# combo-03.net
KiCad netlist of a schematic drawn in EAGLE
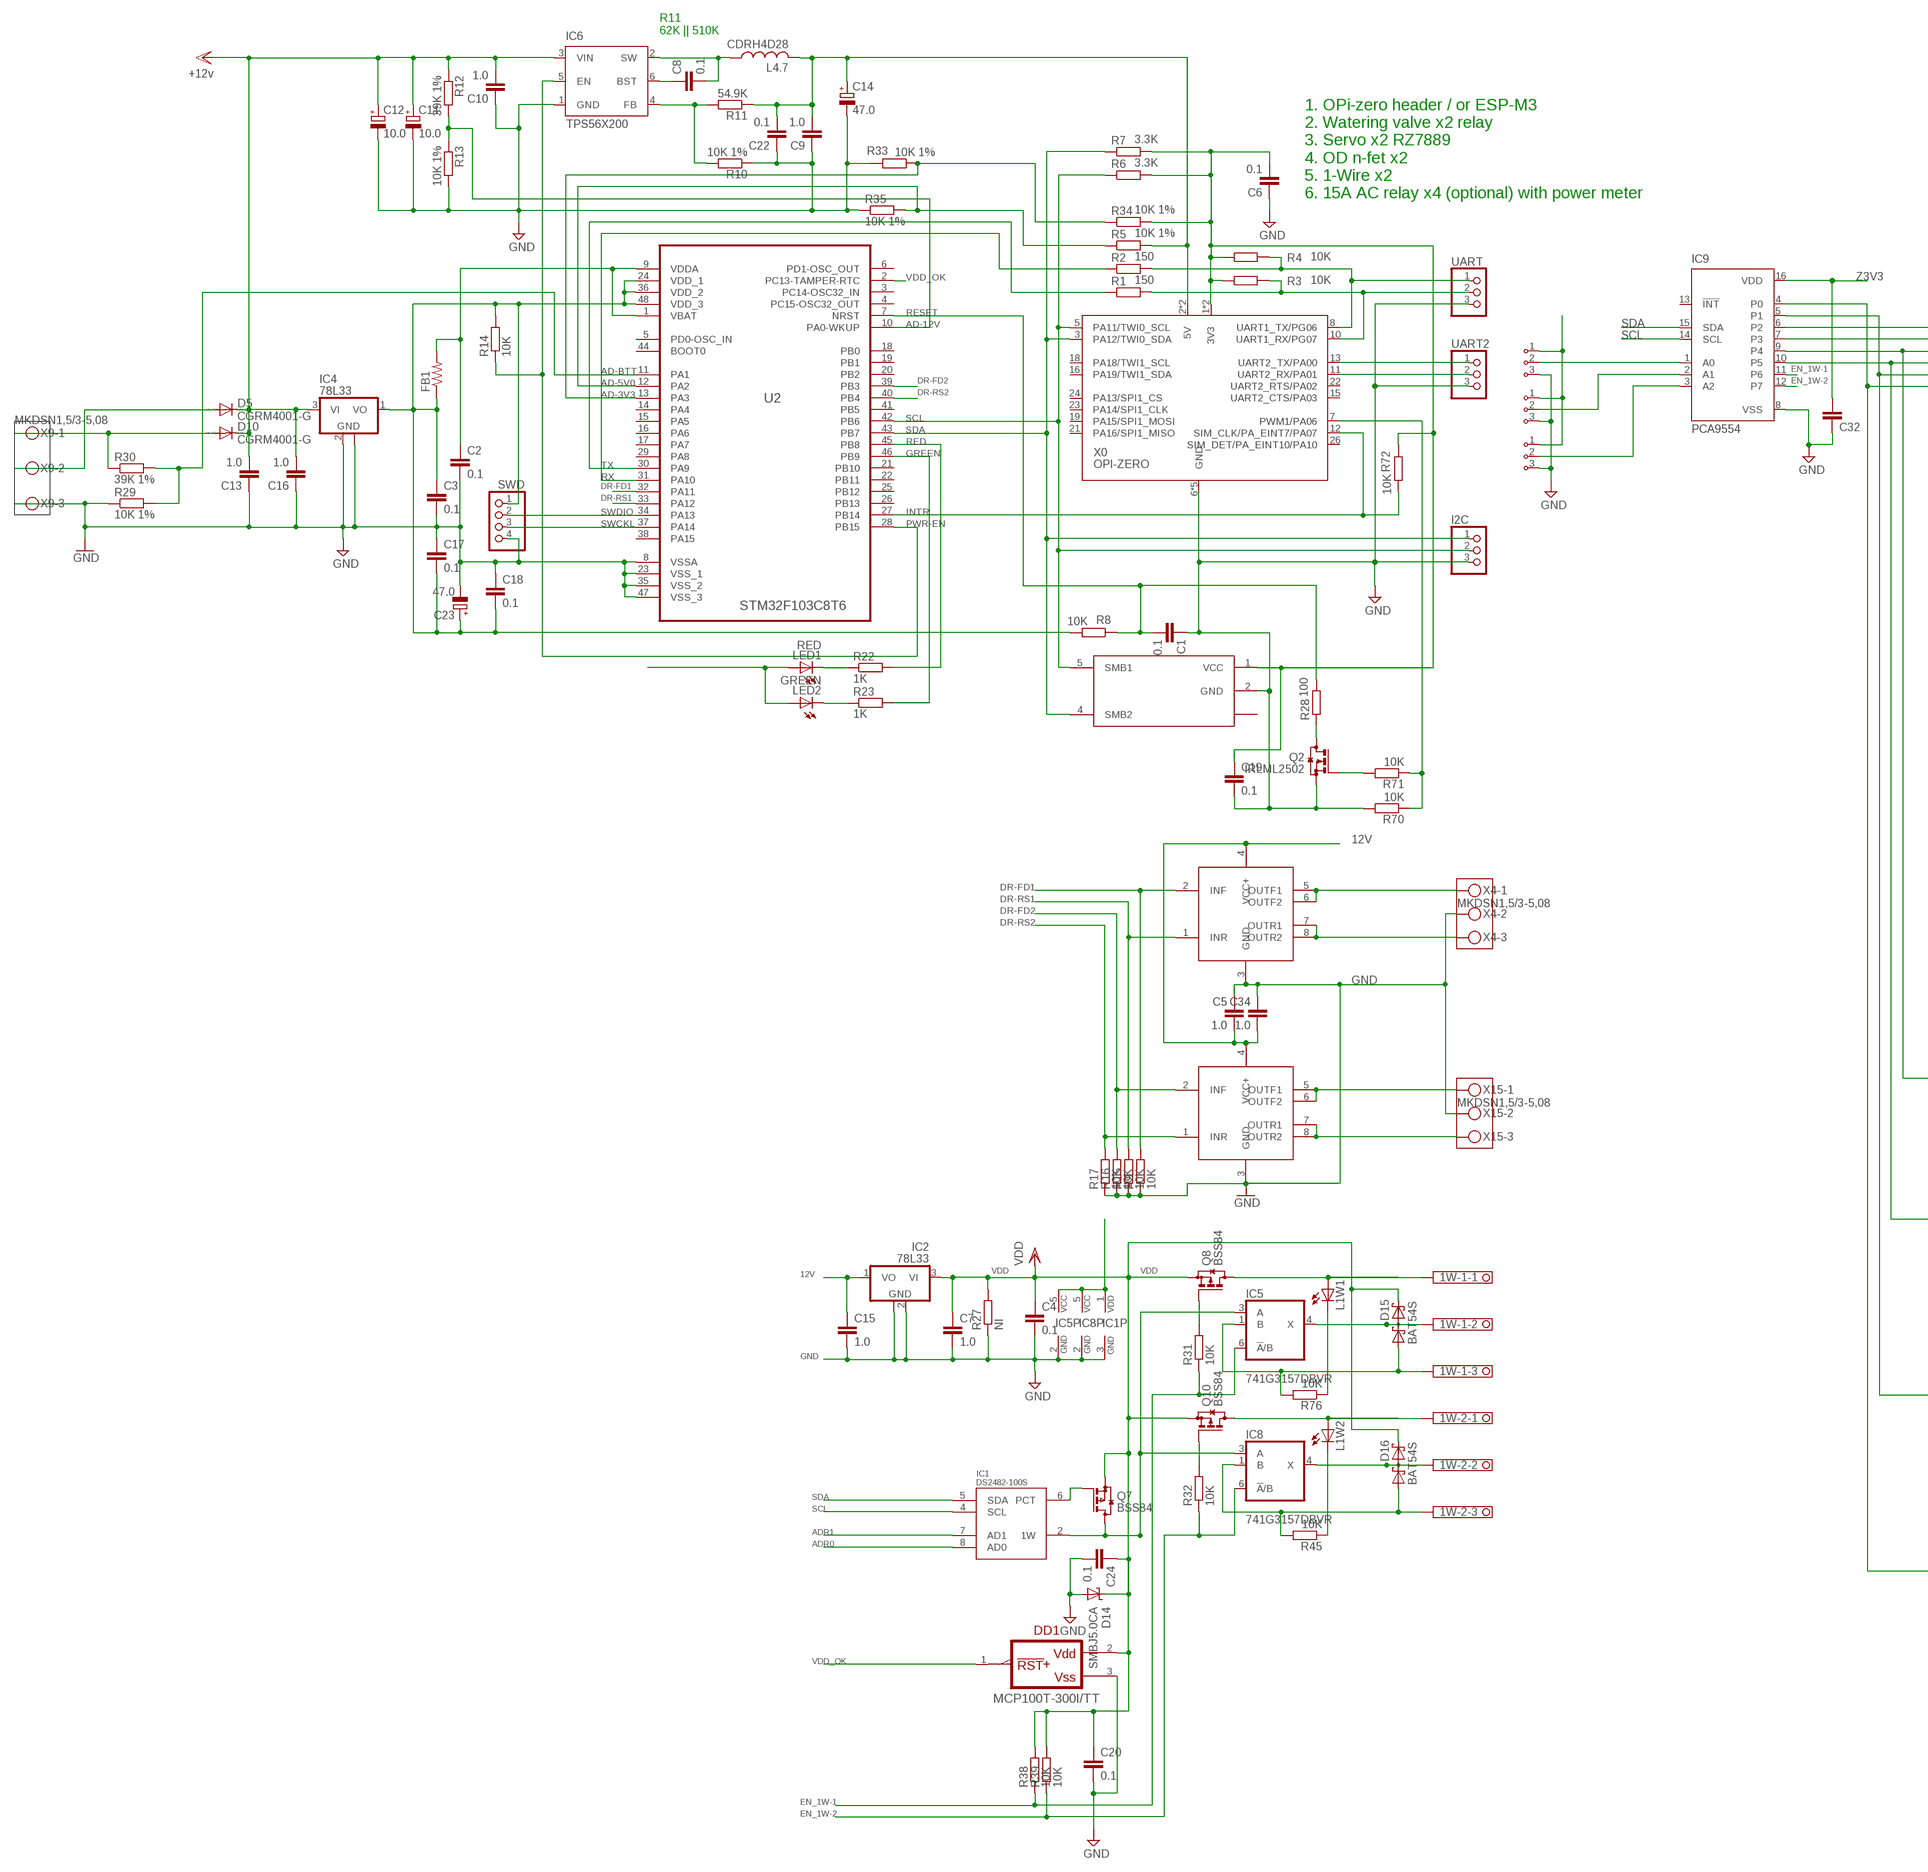
[diagram p0: schematic, sheet 1, part 1 of 2]
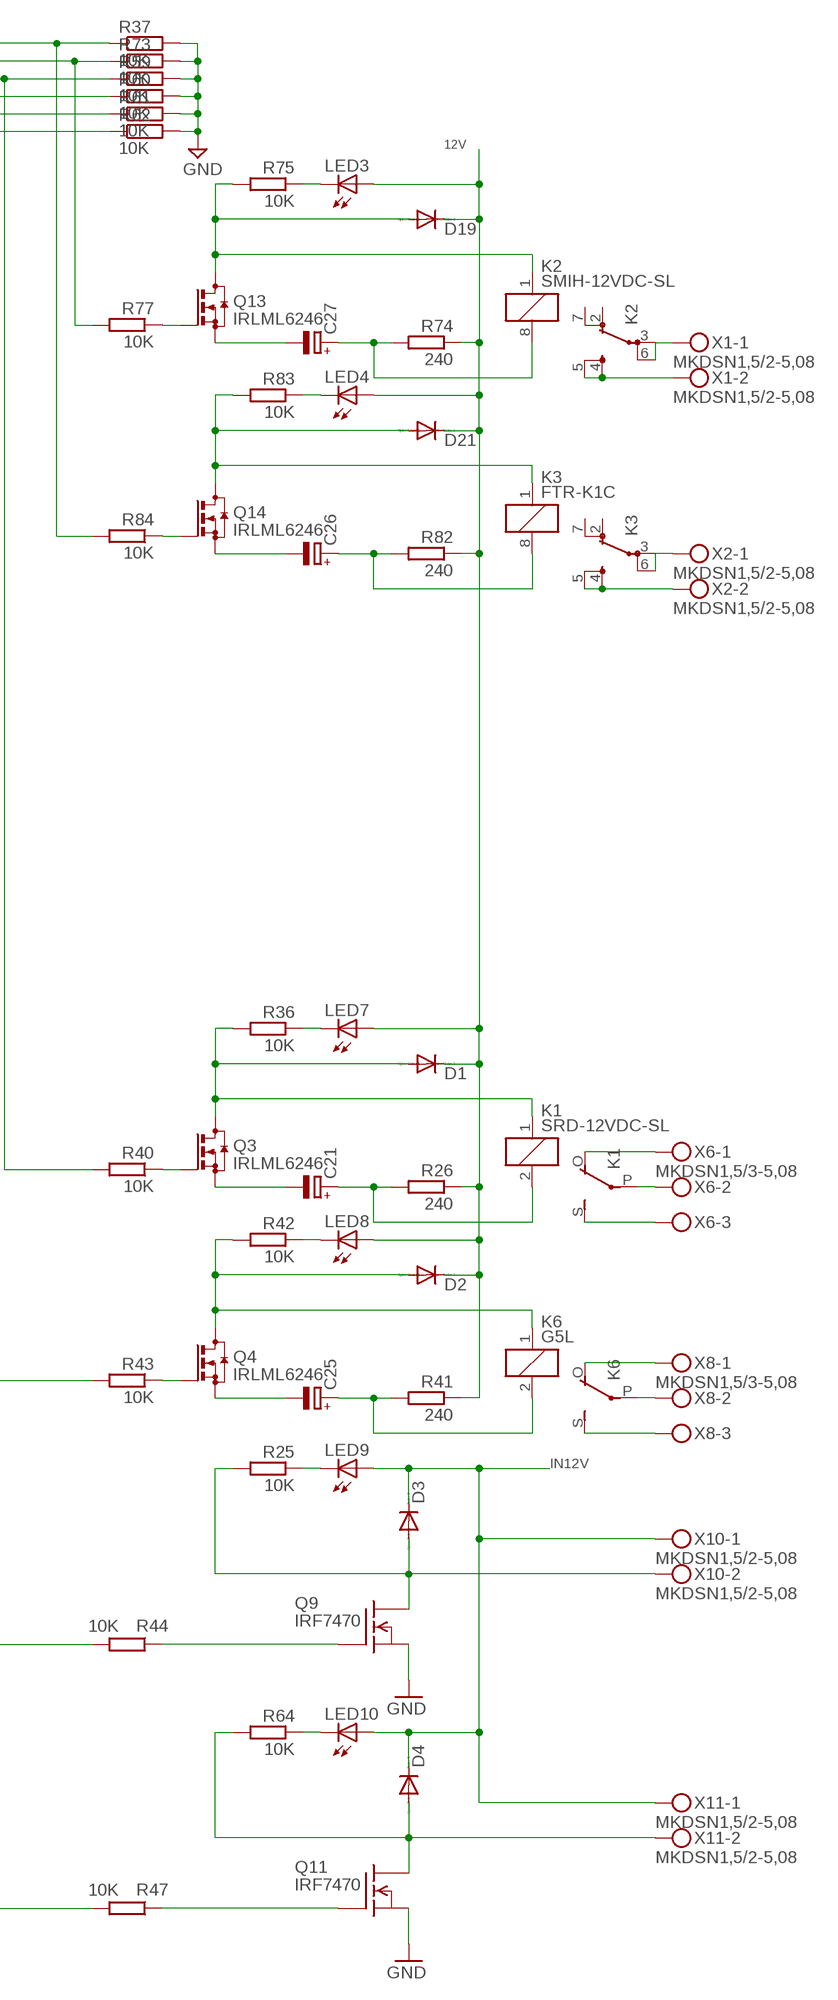
[diagram p1: schematic, sheet 1, part 2 of 2]

(export (version "E")
  (design (tool "Eeschema 10.0.6"))
  (components
    (comp (ref "1W-1")
      (value "1751251")
      (footprint "eagle-import:1751251")
      (libsource (lib "eagle-import") (part "1751251"))
    )
    (comp (ref "1W-2")
      (value "1751251")
      (footprint "eagle-import:1751251")
      (libsource (lib "eagle-import") (part "1751251"))
    )
    (comp (ref "A0")
      (value "ADDR3PIN0603")
      (footprint "eagle-import:0603-3PIN")
      (libsource (lib "eagle-import") (part "ADDR3PIN0603"))
    )
    (comp (ref "A1")
      (value "ADDR3PIN0603")
      (footprint "eagle-import:0603-3PIN")
      (libsource (lib "eagle-import") (part "ADDR3PIN0603"))
    )
    (comp (ref "A2")
      (value "ADDR3PIN0603")
      (footprint "eagle-import:0603-3PIN")
      (libsource (lib "eagle-import") (part "ADDR3PIN0603"))
    )
    (comp (ref "C1")
      (value "0.1")
      (footprint "eagle-import:C0603")
      (libsource (lib "eagle-import") (part "C-EUC0603"))
    )
    (comp (ref "C2")
      (value "0.1")
      (footprint "eagle-import:C0603")
      (libsource (lib "eagle-import") (part "C-EUC0603"))
    )
    (comp (ref "C3")
      (value "0.1")
      (footprint "eagle-import:C0603")
      (libsource (lib "eagle-import") (part "C-EUC0603"))
    )
    (comp (ref "C4")
      (value "0.1")
      (footprint "eagle-import:C0603")
      (libsource (lib "eagle-import") (part "C-EUC0603"))
    )
    (comp (ref "C5")
      (value "1.0")
      (footprint "eagle-import:C0805")
      (libsource (lib "eagle-import") (part "C-EUC0805"))
    )
    (comp (ref "C6")
      (value "0.1")
      (footprint "eagle-import:C0805")
      (libsource (lib "eagle-import") (part "C-EUC0805"))
    )
    (comp (ref "C7")
      (value "1.0")
      (footprint "eagle-import:C0805")
      (libsource (lib "eagle-import") (part "C-EUC0805"))
    )
    (comp (ref "C8")
      (value "0.1")
      (footprint "eagle-import:C0805")
      (libsource (lib "eagle-import") (part "C-EUC0805"))
    )
    (comp (ref "C9")
      (value "1.0")
      (footprint "eagle-import:C0805")
      (libsource (lib "eagle-import") (part "C-EUC0805"))
    )
    (comp (ref "C10")
      (value "1.0")
      (footprint "eagle-import:C1206")
      (libsource (lib "eagle-import") (part "C-EUC1206"))
    )
    (comp (ref "C11")
      (value "10.0")
      (footprint "eagle-import:C_6032-28R")
      (libsource (lib "eagle-import") (part "CPOL-EUC/6032-28R"))
    )
    (comp (ref "C12")
      (value "10.0")
      (footprint "eagle-import:C_6032-28R")
      (libsource (lib "eagle-import") (part "CPOL-EUC/6032-28R"))
    )
    (comp (ref "C13")
      (value "1.0")
      (footprint "eagle-import:C1206")
      (libsource (lib "eagle-import") (part "C-EUC1206"))
    )
    (comp (ref "C14")
      (value "47.0")
      (footprint "eagle-import:B_3528-21R")
      (libsource (lib "eagle-import") (part "CPOL-EUB/3528-21R"))
    )
    (comp (ref "C15")
      (value "1.0")
      (footprint "eagle-import:C0805")
      (libsource (lib "eagle-import") (part "C-EUC0805"))
    )
    (comp (ref "C16")
      (value "1.0")
      (footprint "eagle-import:C1206")
      (libsource (lib "eagle-import") (part "C-EUC1206"))
    )
    (comp (ref "C17")
      (value "0.1")
      (footprint "eagle-import:C0603")
      (libsource (lib "eagle-import") (part "C-EUC0603"))
    )
    (comp (ref "C18")
      (value "0.1")
      (footprint "eagle-import:C0603")
      (libsource (lib "eagle-import") (part "C-EUC0603"))
    )
    (comp (ref "C19")
      (value "0.1")
      (footprint "eagle-import:C0603")
      (libsource (lib "eagle-import") (part "C-EUC0603"))
    )
    (comp (ref "C20")
      (value "0.1")
      (footprint "eagle-import:C0603")
      (libsource (lib "eagle-import") (part "C-EUC0603"))
    )
    (comp (ref "C21")
      (value "CPOL-EUE3.5-8")
      (footprint "eagle-import:E3,5-8")
      (libsource (lib "eagle-import") (part "CPOL-EUE3.5-8"))
    )
    (comp (ref "C22")
      (value "0.1")
      (footprint "eagle-import:C0805")
      (libsource (lib "eagle-import") (part "C-EUC0805"))
    )
    (comp (ref "C23")
      (value "47.0")
      (footprint "eagle-import:B_3528-21R")
      (libsource (lib "eagle-import") (part "CPOL-EUB/3528-21R"))
    )
    (comp (ref "C24")
      (value "0.1")
      (footprint "eagle-import:C0603")
      (libsource (lib "eagle-import") (part "C-EUC0603"))
    )
    (comp (ref "C25")
      (value "CPOL-EUE3.5-8")
      (footprint "eagle-import:E3,5-8")
      (libsource (lib "eagle-import") (part "CPOL-EUE3.5-8"))
    )
    (comp (ref "C26")
      (value "CPOL-EUE3.5-8")
      (footprint "eagle-import:E3,5-8")
      (libsource (lib "eagle-import") (part "CPOL-EUE3.5-8"))
    )
    (comp (ref "C27")
      (value "CPOL-EUE3.5-8")
      (footprint "eagle-import:E3,5-8")
      (libsource (lib "eagle-import") (part "CPOL-EUE3.5-8"))
    )
    (comp (ref "C32")
      (value "C-EUC0805")
      (footprint "eagle-import:C0805")
      (libsource (lib "eagle-import") (part "C-EUC0805"))
    )
    (comp (ref "C34")
      (value "1.0")
      (footprint "eagle-import:C0805")
      (libsource (lib "eagle-import") (part "C-EUC0805"))
    )
    (comp (ref "D1")
      (value "DIODE-SOD123")
      (footprint "eagle-import:SOD123")
      (libsource (lib "eagle-import") (part "DIODE-SOD123"))
    )
    (comp (ref "D2")
      (value "DIODE-SOD123")
      (footprint "eagle-import:SOD123")
      (libsource (lib "eagle-import") (part "DIODE-SOD123"))
    )
    (comp (ref "D3")
      (value "DIODE-SOD123")
      (footprint "eagle-import:SOD123")
      (libsource (lib "eagle-import") (part "DIODE-SOD123"))
    )
    (comp (ref "D4")
      (value "DIODE-SOD123")
      (footprint "eagle-import:SOD123")
      (libsource (lib "eagle-import") (part "DIODE-SOD123"))
    )
    (comp (ref "D5")
      (value "CGRM4001-G")
      (footprint "eagle-import:SOD-123_MINI-SMA")
      (libsource (lib "eagle-import") (part "CGRM400-G1"))
    )
    (comp (ref "D10")
      (value "CGRM4001-G")
      (footprint "eagle-import:SOD-123_MINI-SMA")
      (libsource (lib "eagle-import") (part "CGRM400-G1"))
    )
    (comp (ref "D14")
      (value "SMBJ5.0CA")
      (footprint "eagle-import:SMBJ")
      (libsource (lib "eagle-import") (part "SUPPRESSOR-SMBJ"))
    )
    (comp (ref "D15")
      (value "BAT54S")
      (footprint "eagle-import:SOT23")
      (libsource (lib "eagle-import") (part "BAT54S"))
    )
    (comp (ref "D16")
      (value "BAT54S")
      (footprint "eagle-import:SOT23")
      (libsource (lib "eagle-import") (part "BAT54S"))
    )
    (comp (ref "D19")
      (value "DIODE-SOD123")
      (footprint "eagle-import:SOD123")
      (libsource (lib "eagle-import") (part "DIODE-SOD123"))
    )
    (comp (ref "D21")
      (value "DIODE-SOD123")
      (footprint "eagle-import:SOD123")
      (libsource (lib "eagle-import") (part "DIODE-SOD123"))
    )
    (comp (ref "DD1")
      (value "MCP100T-300I/TT")
      (footprint "eagle-import:SOT23")
      (libsource (lib "eagle-import") (part "MCP100T-300I/TT"))
    )
    (comp (ref "FB1")
      (value "R-US_R0805")
      (footprint "eagle-import:R0805")
      (libsource (lib "eagle-import") (part "R-US_R0805"))
    )
    (comp (ref "I2C")
      (value "PINHD-1X3")
      (footprint "eagle-import:1X03")
      (libsource (lib "eagle-import") (part "PINHD-1X3"))
    )
    (comp (ref "IC1")
      (value "DS2482-100S")
      (footprint "eagle-import:SO08")
      (libsource (lib "eagle-import") (part "DS2482-100S"))
    )
    (comp (ref "IC2")
      (value "78L33")
      (footprint "eagle-import:SOT89")
      (libsource (lib "eagle-import") (part "78LF05"))
    )
    (comp (ref "IC3")
      (value "RZ7889")
      (footprint "eagle-import:SO8")
      (libsource (lib "eagle-import") (part "RZ7889"))
    )
    (comp (ref "IC4")
      (value "78L33")
      (footprint "eagle-import:SOT89")
      (libsource (lib "eagle-import") (part "78LF05"))
    )
    (comp (ref "IC5")
      (value "741G3157DBVR")
      (footprint "eagle-import:DBV_R-PDSO-G6")
      (libsource (lib "eagle-import") (part "741G3157DBVR"))
    )
    (comp (ref "IC6")
      (value "TPS56X200")
      (footprint "eagle-import:TSOT23-6_DDC")
      (libsource (lib "eagle-import") (part "TPS56X200"))
    )
    (comp (ref "IC7")
      (value "LTC1694")
      (footprint "eagle-import:SOT23-5")
      (libsource (lib "eagle-import") (part "LTC1694"))
    )
    (comp (ref "IC8")
      (value "741G3157DBVR")
      (footprint "eagle-import:DBV_R-PDSO-G6")
      (libsource (lib "eagle-import") (part "741G3157DBVR"))
    )
    (comp (ref "IC9")
      (value "PCA9554")
      (footprint "eagle-import:SO16W")
      (fields (field (name "MPN") "PCF8574T/3,512"))
      (libsource (lib "eagle-import") (part "PCF8574T"))
    )
    (comp (ref "IC10")
      (value "RZ7889")
      (footprint "eagle-import:SO8")
      (libsource (lib "eagle-import") (part "RZ7889"))
    )
    (comp (ref "K1")
      (value "SRD-12VDC-SL")
      (footprint "eagle-import:G5LE")
      (libsource (lib "eagle-import") (part "G5L"))
    )
    (comp (ref "K2")
      (value "SMIH-12VDC-SL")
      (footprint "eagle-import:FTR-K1C")
      (libsource (lib "eagle-import") (part "FTR-K1C"))
    )
    (comp (ref "K3")
      (value "FTR-K1C")
      (footprint "eagle-import:FTR-K1C")
      (libsource (lib "eagle-import") (part "FTR-K1C"))
    )
    (comp (ref "K6")
      (value "G5L")
      (footprint "eagle-import:G5LE")
      (libsource (lib "eagle-import") (part "G5L"))
    )
    (comp (ref "L1W1")
      (value "LEDSMT1206")
      (footprint "eagle-import:1206")
      (libsource (lib "eagle-import") (part "LEDSMT1206"))
    )
    (comp (ref "L1W2")
      (value "LEDSMT1206")
      (footprint "eagle-import:1206")
      (libsource (lib "eagle-import") (part "LEDSMT1206"))
    )
    (comp (ref "L4.7")
      (value "CDRH4D28")
      (footprint "eagle-import:CDRH4D28")
      (libsource (lib "eagle-import") (part "CDRH4D28"))
    )
    (comp (ref "LED1")
      (value "RED")
      (footprint "eagle-import:CHIPLED_1206")
      (libsource (lib "eagle-import") (part "LEDCHIPLED_1206"))
    )
    (comp (ref "LED2")
      (value "GREEN")
      (footprint "eagle-import:CHIPLED_1206")
      (libsource (lib "eagle-import") (part "LEDCHIPLED_1206"))
    )
    (comp (ref "LED3")
      (value "LEDSMT1206")
      (footprint "eagle-import:1206")
      (libsource (lib "eagle-import") (part "LEDSMT1206"))
    )
    (comp (ref "LED4")
      (value "LEDSMT1206")
      (footprint "eagle-import:1206")
      (libsource (lib "eagle-import") (part "LEDSMT1206"))
    )
    (comp (ref "LED7")
      (value "LEDSMT1206")
      (footprint "eagle-import:1206")
      (libsource (lib "eagle-import") (part "LEDSMT1206"))
    )
    (comp (ref "LED8")
      (value "LEDSMT1206")
      (footprint "eagle-import:1206")
      (libsource (lib "eagle-import") (part "LEDSMT1206"))
    )
    (comp (ref "LED9")
      (value "LEDSMT1206")
      (footprint "eagle-import:1206")
      (libsource (lib "eagle-import") (part "LEDSMT1206"))
    )
    (comp (ref "LED10")
      (value "LEDSMT1206")
      (footprint "eagle-import:1206")
      (libsource (lib "eagle-import") (part "LEDSMT1206"))
    )
    (comp (ref "Q2")
      (value "IRLML2502")
      (footprint "eagle-import:SOT23")
      (libsource (lib "eagle-import") (part "IRLML2502"))
    )
    (comp (ref "Q3")
      (value "IRLML6246")
      (footprint "eagle-import:SOT23")
      (libsource (lib "eagle-import") (part "BSS123"))
    )
    (comp (ref "Q4")
      (value "IRLML6246")
      (footprint "eagle-import:SOT23")
      (libsource (lib "eagle-import") (part "BSS123"))
    )
    (comp (ref "Q7")
      (value "BSS84")
      (footprint "eagle-import:SOT23")
      (libsource (lib "eagle-import") (part "BSS84"))
    )
    (comp (ref "Q8")
      (value "BSS84")
      (footprint "eagle-import:SOT23")
      (libsource (lib "eagle-import") (part "BSS84"))
    )
    (comp (ref "Q9")
      (value "IRF7470")
      (footprint "eagle-import:SO-8")
      (libsource (lib "eagle-import") (part "FDS5680"))
    )
    (comp (ref "Q10")
      (value "BSS84")
      (footprint "eagle-import:SOT23")
      (libsource (lib "eagle-import") (part "BSS84"))
    )
    (comp (ref "Q11")
      (value "IRF7470")
      (footprint "eagle-import:SO-8")
      (libsource (lib "eagle-import") (part "FDS5680"))
    )
    (comp (ref "Q13")
      (value "IRLML6246")
      (footprint "eagle-import:SOT23")
      (libsource (lib "eagle-import") (part "BSS123"))
    )
    (comp (ref "Q14")
      (value "IRLML6246")
      (footprint "eagle-import:SOT23")
      (libsource (lib "eagle-import") (part "BSS123"))
    )
    (comp (ref "R1")
      (value "150")
      (footprint "eagle-import:R0603")
      (libsource (lib "eagle-import") (part "R-EU_R0603"))
    )
    (comp (ref "R2")
      (value "150")
      (footprint "eagle-import:R0603")
      (libsource (lib "eagle-import") (part "R-EU_R0603"))
    )
    (comp (ref "R3")
      (value "10K")
      (footprint "eagle-import:R0603")
      (libsource (lib "eagle-import") (part "R-EU_R0603"))
    )
    (comp (ref "R4")
      (value "10K")
      (footprint "eagle-import:R0603")
      (libsource (lib "eagle-import") (part "R-EU_R0603"))
    )
    (comp (ref "R5")
      (value "10K 1%")
      (footprint "eagle-import:R0603")
      (libsource (lib "eagle-import") (part "R-EU_R0603"))
    )
    (comp (ref "R6")
      (value "3.3K")
      (footprint "eagle-import:R0603")
      (libsource (lib "eagle-import") (part "R-EU_R0603"))
    )
    (comp (ref "R7")
      (value "3.3K")
      (footprint "eagle-import:R0603")
      (libsource (lib "eagle-import") (part "R-EU_R0603"))
    )
    (comp (ref "R8")
      (value "10K")
      (footprint "eagle-import:R0603")
      (libsource (lib "eagle-import") (part "R-EU_R0603"))
    )
    (comp (ref "R9")
      (value "10K")
      (footprint "eagle-import:R0603")
      (libsource (lib "eagle-import") (part "R-EU_R0603"))
    )
    (comp (ref "R10")
      (value "10K 1%")
      (footprint "eagle-import:R0603")
      (libsource (lib "eagle-import") (part "R-EU_R0603"))
    )
    (comp (ref "R11")
      (value "54.9K")
      (footprint "eagle-import:R0603")
      (libsource (lib "eagle-import") (part "R-EU_R0603"))
    )
    (comp (ref "R12")
      (value "39K 1%")
      (footprint "eagle-import:R0603")
      (libsource (lib "eagle-import") (part "R-EU_R0603"))
    )
    (comp (ref "R13")
      (value "10K 1%")
      (footprint "eagle-import:R0603")
      (libsource (lib "eagle-import") (part "R-EU_R0603"))
    )
    (comp (ref "R14")
      (value "10K")
      (footprint "eagle-import:R0603")
      (libsource (lib "eagle-import") (part "R-EU_R0603"))
    )
    (comp (ref "R15")
      (value "10K")
      (footprint "eagle-import:R0603")
      (libsource (lib "eagle-import") (part "R-EU_R0603"))
    )
    (comp (ref "R16")
      (value "10K")
      (footprint "eagle-import:R0603")
      (libsource (lib "eagle-import") (part "R-EU_R0603"))
    )
    (comp (ref "R17")
      (value "10K")
      (footprint "eagle-import:R0603")
      (libsource (lib "eagle-import") (part "R-EU_R0603"))
    )
    (comp (ref "R22")
      (value "1K")
      (footprint "eagle-import:R0603")
      (libsource (lib "eagle-import") (part "R-EU_R0603"))
    )
    (comp (ref "R23")
      (value "1K")
      (footprint "eagle-import:R0603")
      (libsource (lib "eagle-import") (part "R-EU_R0603"))
    )
    (comp (ref "R25")
      (value "10K")
      (footprint "eagle-import:R0603")
      (libsource (lib "eagle-import") (part "R-EU_R0603"))
    )
    (comp (ref "R26")
      (value "240")
      (footprint "eagle-import:R1206")
      (libsource (lib "eagle-import") (part "R-EU_R1206"))
    )
    (comp (ref "R27")
      (value "NI")
      (footprint "eagle-import:R0603")
      (libsource (lib "eagle-import") (part "R-EU_R0603"))
    )
    (comp (ref "R28")
      (value "100")
      (footprint "eagle-import:R0603")
      (libsource (lib "eagle-import") (part "R-EU_R0603"))
    )
    (comp (ref "R29")
      (value "10K 1%")
      (footprint "eagle-import:R0603")
      (libsource (lib "eagle-import") (part "R-EU_R0603"))
    )
    (comp (ref "R30")
      (value "39K 1%")
      (footprint "eagle-import:R0603")
      (libsource (lib "eagle-import") (part "R-EU_R0603"))
    )
    (comp (ref "R31")
      (value "10K")
      (footprint "eagle-import:R0603")
      (libsource (lib "eagle-import") (part "R-EU_R0603"))
    )
    (comp (ref "R32")
      (value "10K")
      (footprint "eagle-import:R0603")
      (libsource (lib "eagle-import") (part "R-EU_R0603"))
    )
    (comp (ref "R33")
      (value "10K 1%")
      (footprint "eagle-import:R0603")
      (libsource (lib "eagle-import") (part "R-EU_R0603"))
    )
    (comp (ref "R34")
      (value "10K 1%")
      (footprint "eagle-import:R0603")
      (libsource (lib "eagle-import") (part "R-EU_R0603"))
    )
    (comp (ref "R35")
      (value "10K 1%")
      (footprint "eagle-import:R0603")
      (libsource (lib "eagle-import") (part "R-EU_R0603"))
    )
    (comp (ref "R36")
      (value "10K")
      (footprint "eagle-import:R0603")
      (libsource (lib "eagle-import") (part "R-EU_R0603"))
    )
    (comp (ref "R37")
      (value "10K")
      (footprint "eagle-import:R0603")
      (libsource (lib "eagle-import") (part "R-EU_R0603"))
    )
    (comp (ref "R38")
      (value "10K")
      (footprint "eagle-import:R0603")
      (libsource (lib "eagle-import") (part "R-EU_R0603"))
    )
    (comp (ref "R39")
      (value "10K")
      (footprint "eagle-import:R0603")
      (libsource (lib "eagle-import") (part "R-EU_R0603"))
    )
    (comp (ref "R40")
      (value "10K")
      (footprint "eagle-import:R0603")
      (libsource (lib "eagle-import") (part "R-EU_R0603"))
    )
    (comp (ref "R41")
      (value "240")
      (footprint "eagle-import:R1206")
      (libsource (lib "eagle-import") (part "R-EU_R1206"))
    )
    (comp (ref "R42")
      (value "10K")
      (footprint "eagle-import:R0603")
      (libsource (lib "eagle-import") (part "R-EU_R0603"))
    )
    (comp (ref "R43")
      (value "10K")
      (footprint "eagle-import:R0603")
      (libsource (lib "eagle-import") (part "R-EU_R0603"))
    )
    (comp (ref "R44")
      (value "10K")
      (footprint "eagle-import:R0603")
      (libsource (lib "eagle-import") (part "R-EU_R0603"))
    )
    (comp (ref "R45")
      (value "10K")
      (footprint "eagle-import:R0603")
      (libsource (lib "eagle-import") (part "R-EU_R0603"))
    )
    (comp (ref "R47")
      (value "10K")
      (footprint "eagle-import:R0603")
      (libsource (lib "eagle-import") (part "R-EU_R0603"))
    )
    (comp (ref "R59")
      (value "10K")
      (footprint "eagle-import:R0603")
      (libsource (lib "eagle-import") (part "R-EU_R0603"))
    )
    (comp (ref "R60")
      (value "10K")
      (footprint "eagle-import:R0603")
      (libsource (lib "eagle-import") (part "R-EU_R0603"))
    )
    (comp (ref "R61")
      (value "10K")
      (footprint "eagle-import:R0603")
      (libsource (lib "eagle-import") (part "R-EU_R0603"))
    )
    (comp (ref "R62")
      (value "10K")
      (footprint "eagle-import:R0603")
      (libsource (lib "eagle-import") (part "R-EU_R0603"))
    )
    (comp (ref "R64")
      (value "10K")
      (footprint "eagle-import:R0603")
      (libsource (lib "eagle-import") (part "R-EU_R0603"))
    )
    (comp (ref "R70")
      (value "10K")
      (footprint "eagle-import:R0603")
      (libsource (lib "eagle-import") (part "R-EU_R0603"))
    )
    (comp (ref "R71")
      (value "10K")
      (footprint "eagle-import:R0603")
      (libsource (lib "eagle-import") (part "R-EU_R0603"))
    )
    (comp (ref "R72")
      (value "10K")
      (footprint "eagle-import:R0603")
      (libsource (lib "eagle-import") (part "R-EU_R0603"))
    )
    (comp (ref "R73")
      (value "10K")
      (footprint "eagle-import:R0603")
      (libsource (lib "eagle-import") (part "R-EU_R0603"))
    )
    (comp (ref "R74")
      (value "240")
      (footprint "eagle-import:R1206")
      (libsource (lib "eagle-import") (part "R-EU_R1206"))
    )
    (comp (ref "R75")
      (value "10K")
      (footprint "eagle-import:R0603")
      (libsource (lib "eagle-import") (part "R-EU_R0603"))
    )
    (comp (ref "R76")
      (value "10K")
      (footprint "eagle-import:R0603")
      (libsource (lib "eagle-import") (part "R-EU_R0603"))
    )
    (comp (ref "R77")
      (value "10K")
      (footprint "eagle-import:R0603")
      (libsource (lib "eagle-import") (part "R-EU_R0603"))
    )
    (comp (ref "R82")
      (value "240")
      (footprint "eagle-import:R1206")
      (libsource (lib "eagle-import") (part "R-EU_R1206"))
    )
    (comp (ref "R83")
      (value "10K")
      (footprint "eagle-import:R0603")
      (libsource (lib "eagle-import") (part "R-EU_R0603"))
    )
    (comp (ref "R84")
      (value "10K")
      (footprint "eagle-import:R0603")
      (libsource (lib "eagle-import") (part "R-EU_R0603"))
    )
    (comp (ref "SWD")
      (value "PINHD-1X4")
      (footprint "eagle-import:1X04")
      (libsource (lib "eagle-import") (part "PINHD-1X4"))
    )
    (comp (ref "U2")
      (value "STM32F103C8T6")
      (footprint "eagle-import:QFP50P900X900X160-48N")
      (fields (field (name "MPN") "STM32F100CBT6B"))
      (libsource (lib "eagle-import") (part "STM32F100CBT6B"))
    )
    (comp (ref "UART")
      (value "PINHD-1X3")
      (footprint "eagle-import:1X03")
      (libsource (lib "eagle-import") (part "PINHD-1X3"))
    )
    (comp (ref "UART2")
      (value "PINHD-1X3")
      (footprint "eagle-import:1X03")
      (libsource (lib "eagle-import") (part "PINHD-1X3"))
    )
    (comp (ref "X0")
      (value "OPI-ZERO")
      (footprint "eagle-import:OPI0")
      (libsource (lib "eagle-import") (part "OPI-ZERO"))
    )
    (comp (ref "X1")
      (value "MKDSN1,5/2-5,08")
      (footprint "eagle-import:MKDSN1,5_2-5,08")
      (libsource (lib "eagle-import") (part "MKDSN1,5/2-5,08"))
    )
    (comp (ref "X2")
      (value "MKDSN1,5/2-5,08")
      (footprint "eagle-import:MKDSN1,5_2-5,08")
      (libsource (lib "eagle-import") (part "MKDSN1,5/2-5,08"))
    )
    (comp (ref "X4")
      (value "MKDSN1,5/3-5,08")
      (footprint "eagle-import:MKDSN1,5_3-5,08")
      (libsource (lib "eagle-import") (part "MKDSN1,5/3-5,08"))
    )
    (comp (ref "X6")
      (value "MKDSN1,5/3-5,08")
      (footprint "eagle-import:MKDSN1,5_3-5,08")
      (libsource (lib "eagle-import") (part "MKDSN1,5/3-5,08"))
    )
    (comp (ref "X8")
      (value "MKDSN1,5/3-5,08")
      (footprint "eagle-import:MKDSN1,5_3-5,08")
      (libsource (lib "eagle-import") (part "MKDSN1,5/3-5,08"))
    )
    (comp (ref "X9")
      (value "MKDSN1,5/3-5,08")
      (footprint "eagle-import:MKDSN1,5_3-5,08")
      (libsource (lib "eagle-import") (part "MKDSN1,5/3-5,08"))
    )
    (comp (ref "X10")
      (value "MKDSN1,5/2-5,08")
      (footprint "eagle-import:MKDSN1,5_2-5,08")
      (libsource (lib "eagle-import") (part "MKDSN1,5/2-5,08"))
    )
    (comp (ref "X11")
      (value "MKDSN1,5/2-5,08")
      (footprint "eagle-import:MKDSN1,5_2-5,08")
      (libsource (lib "eagle-import") (part "MKDSN1,5/2-5,08"))
    )
    (comp (ref "X15")
      (value "MKDSN1,5/3-5,08")
      (footprint "eagle-import:MKDSN1,5_3-5,08")
      (libsource (lib "eagle-import") (part "MKDSN1,5/3-5,08"))
    )
  )
  (nets
    (net (code "1") (name "+12v") (class "Default")
      (node (ref "C10") (pin "2") (pinfunction "2_2") (pintype "passive"))
      (node (ref "C11") (pin "+") (pinfunction "+_+") (pintype "passive"))
      (node (ref "C12") (pin "+") (pinfunction "+_+") (pintype "passive"))
      (node (ref "C13") (pin "2") (pinfunction "2_2") (pintype "passive"))
      (node (ref "C15") (pin "1") (pinfunction "1_1") (pintype "passive"))
      (node (ref "C16") (pin "2") (pinfunction "2_2") (pintype "passive"))
      (node (ref "C34") (pin "2") (pinfunction "2_2") (pintype "passive"))
      (node (ref "C5") (pin "2") (pinfunction "2_2") (pintype "passive"))
      (node (ref "D1") (pin "C") (pinfunction "C_C") (pintype "passive"))
      (node (ref "D10") (pin "C") (pinfunction "C_C") (pintype "passive"))
      (node (ref "D19") (pin "C") (pinfunction "C_C") (pintype "passive"))
      (node (ref "D2") (pin "C") (pinfunction "C_C") (pintype "passive"))
      (node (ref "D21") (pin "C") (pinfunction "C_C") (pintype "passive"))
      (node (ref "D5") (pin "C") (pinfunction "C_C") (pintype "passive"))
      (node (ref "IC10") (pin "4") (pinfunction "VCC+_4") (pintype "bidirectional"))
      (node (ref "IC2") (pin "1") (pinfunction "VO_1") (pintype "passive"))
      (node (ref "IC3") (pin "4") (pinfunction "VCC+_4") (pintype "bidirectional"))
      (node (ref "IC4") (pin "3") (pinfunction "VI_3") (pintype "input"))
      (node (ref "IC6") (pin "3") (pinfunction "VIN_3") (pintype "input"))
      (node (ref "LED3") (pin "A") (pinfunction "A_A") (pintype "passive"))
      (node (ref "LED4") (pin "A") (pinfunction "A_A") (pintype "passive"))
      (node (ref "LED7") (pin "A") (pinfunction "A_A") (pintype "passive"))
      (node (ref "LED8") (pin "A") (pinfunction "A_A") (pintype "passive"))
      (node (ref "R12") (pin "1") (pinfunction "1_1") (pintype "passive"))
      (node (ref "R26") (pin "1") (pinfunction "1_1") (pintype "passive"))
      (node (ref "R41") (pin "1") (pinfunction "1_1") (pintype "passive"))
      (node (ref "R74") (pin "1") (pinfunction "1_1") (pintype "passive"))
      (node (ref "R82") (pin "1") (pinfunction "1_1") (pintype "passive"))
    )
    (net (code "2") (name "/AD-3V3") (class "Default")
      (node (ref "R33") (pin "1") (pinfunction "1_1") (pintype "passive"))
      (node (ref "R34") (pin "1") (pinfunction "1_1") (pintype "passive"))
      (node (ref "U2") (pin "13") (pinfunction "PA3_13") (pintype "bidirectional"))
    )
    (net (code "3") (name "/AD-5V0") (class "Default")
      (node (ref "R35") (pin "2") (pinfunction "2_2") (pintype "passive"))
      (node (ref "R5") (pin "1") (pinfunction "1_1") (pintype "passive"))
      (node (ref "U2") (pin "12") (pinfunction "PA2_12") (pintype "bidirectional"))
    )
    (net (code "4") (name "/AD-12V") (class "Default")
      (node (ref "R12") (pin "2") (pinfunction "2_2") (pintype "passive"))
      (node (ref "R13") (pin "1") (pinfunction "1_1") (pintype "passive"))
      (node (ref "U2") (pin "10") (pinfunction "PA0-WKUP_10") (pintype "bidirectional"))
    )
    (net (code "5") (name "/AD-BTT") (class "Default")
      (node (ref "R29") (pin "2") (pinfunction "2_2") (pintype "passive"))
      (node (ref "R30") (pin "2") (pinfunction "2_2") (pintype "passive"))
      (node (ref "U2") (pin "11") (pinfunction "PA1_11") (pintype "bidirectional"))
    )
    (net (code "6") (name "/ADR0") (class "Default")
      (node (ref "A2") (pin "2") (pinfunction "P$1_2") (pintype "bidirectional"))
      (node (ref "IC1") (pin "8") (pinfunction "AD0_8") (pintype "input"))
      (node (ref "IC9") (pin "1") (pinfunction "A0_1") (pintype "input"))
    )
    (net (code "7") (name "/ADR1") (class "Default")
      (node (ref "A1") (pin "2") (pinfunction "P$1_2") (pintype "bidirectional"))
      (node (ref "IC1") (pin "7") (pinfunction "AD1_7") (pintype "input"))
      (node (ref "IC9") (pin "2") (pinfunction "A1_2") (pintype "input"))
    )
    (net (code "8") (name "/DR-FD1") (class "Default")
      (node (ref "IC3") (pin "2") (pinfunction "INF_2") (pintype "bidirectional"))
      (node (ref "R9") (pin "2") (pinfunction "2_2") (pintype "passive"))
      (node (ref "U2") (pin "32") (pinfunction "PA11_32") (pintype "bidirectional"))
    )
    (net (code "9") (name "/DR-FD2") (class "Default")
      (node (ref "IC10") (pin "2") (pinfunction "INF_2") (pintype "bidirectional"))
      (node (ref "R16") (pin "2") (pinfunction "2_2") (pintype "passive"))
      (node (ref "U2") (pin "39") (pinfunction "PB3_39") (pintype "bidirectional"))
    )
    (net (code "10") (name "/DR-RS1") (class "Default")
      (node (ref "IC3") (pin "1") (pinfunction "INR_1") (pintype "bidirectional"))
      (node (ref "R15") (pin "2") (pinfunction "2_2") (pintype "passive"))
      (node (ref "U2") (pin "33") (pinfunction "PA12_33") (pintype "bidirectional"))
    )
    (net (code "11") (name "/DR-RS2") (class "Default")
      (node (ref "IC10") (pin "1") (pinfunction "INR_1") (pintype "bidirectional"))
      (node (ref "R17") (pin "2") (pinfunction "2_2") (pintype "passive"))
      (node (ref "U2") (pin "40") (pinfunction "PB4_40") (pintype "bidirectional"))
    )
    (net (code "12") (name "/EN_1W-1") (class "Default")
      (node (ref "IC5") (pin "6") (pinfunction "~{A}/B_6") (pintype "input"))
      (node (ref "IC9") (pin "11") (pinfunction "P6_11") (pintype "bidirectional"))
      (node (ref "R31") (pin "1") (pinfunction "1_1") (pintype "passive"))
      (node (ref "R38") (pin "1") (pinfunction "1_1") (pintype "passive"))
    )
    (net (code "13") (name "/EN_1W-2") (class "Default")
      (node (ref "IC8") (pin "6") (pinfunction "~{A}/B_6") (pintype "input"))
      (node (ref "IC9") (pin "12") (pinfunction "P7_12") (pintype "bidirectional"))
      (node (ref "R32") (pin "1") (pinfunction "1_1") (pintype "passive"))
      (node (ref "R39") (pin "1") (pinfunction "1_1") (pintype "passive"))
    )
    (net (code "14") (name "/GREEN") (class "Default")
      (node (ref "R23") (pin "2") (pinfunction "2_2") (pintype "passive"))
      (node (ref "U2") (pin "46") (pinfunction "PB9_46") (pintype "bidirectional"))
    )
    (net (code "15") (name "/IN12V") (class "Default")
      (node (ref "D3") (pin "C") (pinfunction "C_C") (pintype "passive"))
      (node (ref "D4") (pin "C") (pinfunction "C_C") (pintype "passive"))
      (node (ref "D5") (pin "A") (pinfunction "A_A") (pintype "passive"))
      (node (ref "LED10") (pin "A") (pinfunction "A_A") (pintype "passive"))
      (node (ref "LED9") (pin "A") (pinfunction "A_A") (pintype "passive"))
      (node (ref "X10") (pin "1") (pinfunction "KL_1") (pintype "passive"))
      (node (ref "X11") (pin "1") (pinfunction "KL_1") (pintype "passive"))
      (node (ref "X9") (pin "2") (pinfunction "KL_2") (pintype "passive"))
    )
    (net (code "16") (name "/INTR") (class "Default")
      (node (ref "R72") (pin "2") (pinfunction "2_2") (pintype "passive"))
      (node (ref "U2") (pin "27") (pinfunction "PB14_27") (pintype "bidirectional"))
      (node (ref "X0") (pin "12") (pinfunction "SIM_CLK/PA_EINT7/PA07_12") (pintype "bidirectional"))
    )
    (net (code "17") (name "/PWR-EN") (class "Default")
      (node (ref "IC6") (pin "5") (pinfunction "EN_5") (pintype "input"))
      (node (ref "R14") (pin "1") (pinfunction "1_1") (pintype "passive"))
      (node (ref "U2") (pin "28") (pinfunction "PB15_28") (pintype "bidirectional"))
    )
    (net (code "18") (name "/RED") (class "Default")
      (node (ref "R22") (pin "2") (pinfunction "2_2") (pintype "passive"))
      (node (ref "U2") (pin "45") (pinfunction "PB8_45") (pintype "bidirectional"))
    )
    (net (code "19") (name "/RESET") (class "Default")
      (node (ref "C1") (pin "2") (pinfunction "2_2") (pintype "passive"))
      (node (ref "R28") (pin "2") (pinfunction "2_2") (pintype "passive"))
      (node (ref "R8") (pin "1") (pinfunction "1_1") (pintype "passive"))
      (node (ref "U2") (pin "7") (pinfunction "NRST_7") (pintype "bidirectional"))
    )
    (net (code "20") (name "/RX") (class "Default")
      (node (ref "R2") (pin "1") (pinfunction "1_1") (pintype "passive"))
      (node (ref "U2") (pin "31") (pinfunction "PA10_31") (pintype "bidirectional"))
    )
    (net (code "21") (name "/SCL") (class "Default")
      (node (ref "I2C") (pin "2") (pinfunction "2_2") (pintype "passive"))
      (node (ref "IC1") (pin "4") (pinfunction "SCL_4") (pintype "input"))
      (node (ref "IC7") (pin "5") (pinfunction "SMB1_5") (pintype "bidirectional"))
      (node (ref "IC9") (pin "14") (pinfunction "SCL_14") (pintype "input"))
      (node (ref "R6") (pin "1") (pinfunction "1_1") (pintype "passive"))
      (node (ref "U2") (pin "42") (pinfunction "PB6_42") (pintype "bidirectional"))
      (node (ref "X0") (pin "5") (pinfunction "PA11/TWI0_SCL_5") (pintype "bidirectional"))
    )
    (net (code "22") (name "/SDA") (class "Default")
      (node (ref "I2C") (pin "1") (pinfunction "1_1") (pintype "passive"))
      (node (ref "IC1") (pin "5") (pinfunction "SDA_5") (pintype "bidirectional"))
      (node (ref "IC7") (pin "4") (pinfunction "SMB2_4") (pintype "bidirectional"))
      (node (ref "IC9") (pin "15") (pinfunction "SDA_15") (pintype "bidirectional"))
      (node (ref "R7") (pin "1") (pinfunction "1_1") (pintype "passive"))
      (node (ref "U2") (pin "43") (pinfunction "PB7_43") (pintype "bidirectional"))
      (node (ref "X0") (pin "3") (pinfunction "PA12/TWI0_SDA_3") (pintype "bidirectional"))
    )
    (net (code "23") (name "/SWCKL") (class "Default")
      (node (ref "SWD") (pin "3") (pinfunction "3_3") (pintype "passive"))
      (node (ref "U2") (pin "37") (pinfunction "PA14_37") (pintype "bidirectional"))
    )
    (net (code "24") (name "/SWDIO") (class "Default")
      (node (ref "SWD") (pin "2") (pinfunction "2_2") (pintype "passive"))
      (node (ref "U2") (pin "34") (pinfunction "PA13_34") (pintype "bidirectional"))
    )
    (net (code "25") (name "/TX") (class "Default")
      (node (ref "R1") (pin "1") (pinfunction "1_1") (pintype "passive"))
      (node (ref "U2") (pin "30") (pinfunction "PA9_30") (pintype "bidirectional"))
    )
    (net (code "26") (name "/VDD_OK") (class "Default")
      (node (ref "DD1") (pin "1") (pinfunction "~{RST}_1") (pintype "passive"))
      (node (ref "U2") (pin "2") (pinfunction "PC13-TAMPER-RTC_2") (pintype "bidirectional"))
    )
    (net (code "27") (name "/Z3V3") (class "Default")
      (node (ref "A0") (pin "1") (pinfunction "P$2_1") (pintype "power_in"))
      (node (ref "A1") (pin "1") (pinfunction "P$2_1") (pintype "power_in"))
      (node (ref "A2") (pin "1") (pinfunction "P$2_1") (pintype "power_in"))
      (node (ref "C19") (pin "1") (pinfunction "1_1") (pintype "passive"))
      (node (ref "C32") (pin "2") (pinfunction "2_2") (pintype "passive"))
      (node (ref "C6") (pin "2") (pinfunction "2_2") (pintype "passive"))
      (node (ref "IC1") (pin "1") (pinfunction "VDD_1") (pintype "power_in"))
      (node (ref "IC5") (pin "5") (pinfunction "VCC_5") (pintype "power_in"))
      (node (ref "IC7") (pin "1") (pinfunction "VCC_1") (pintype "power_in"))
      (node (ref "IC8") (pin "5") (pinfunction "VCC_5") (pintype "power_in"))
      (node (ref "IC9") (pin "16") (pinfunction "VDD_16") (pintype "power_in"))
      (node (ref "R3") (pin "1") (pinfunction "1_1") (pintype "passive"))
      (node (ref "R34") (pin "2") (pinfunction "2_2") (pintype "passive"))
      (node (ref "R4") (pin "1") (pinfunction "1_1") (pintype "passive"))
      (node (ref "R6") (pin "2") (pinfunction "2_2") (pintype "passive"))
      (node (ref "R7") (pin "2") (pinfunction "2_2") (pintype "passive"))
      (node (ref "R72") (pin "1") (pinfunction "1_1") (pintype "passive"))
      (node (ref "X0") (pin "1") (pinfunction "3V3_1") (pintype "power_in"))
      (node (ref "X0") (pin "17") (pinfunction "3V3_17") (pintype "power_in"))
    )
    (net (code "28") (name "GND") (class "Default")
      (node (ref "1W-1") (pin "3") (pinfunction "K_3") (pintype "passive"))
      (node (ref "1W-2") (pin "3") (pinfunction "K_3") (pintype "passive"))
      (node (ref "A0") (pin "3") (pinfunction "P$3_3") (pintype "power_in"))
      (node (ref "A1") (pin "3") (pinfunction "P$3_3") (pintype "power_in"))
      (node (ref "A2") (pin "3") (pinfunction "P$3_3") (pintype "power_in"))
      (node (ref "C1") (pin "1") (pinfunction "1_1") (pintype "passive"))
      (node (ref "C10") (pin "1") (pinfunction "1_1") (pintype "passive"))
      (node (ref "C11") (pin "-") (pinfunction "-_-") (pintype "passive"))
      (node (ref "C12") (pin "-") (pinfunction "-_-") (pintype "passive"))
      (node (ref "C13") (pin "1") (pinfunction "1_1") (pintype "passive"))
      (node (ref "C14") (pin "-") (pinfunction "-_-") (pintype "passive"))
      (node (ref "C15") (pin "2") (pinfunction "2_2") (pintype "passive"))
      (node (ref "C16") (pin "1") (pinfunction "1_1") (pintype "passive"))
      (node (ref "C17") (pin "1") (pinfunction "1_1") (pintype "passive"))
      (node (ref "C18") (pin "1") (pinfunction "1_1") (pintype "passive"))
      (node (ref "C19") (pin "2") (pinfunction "2_2") (pintype "passive"))
      (node (ref "C2") (pin "2") (pinfunction "2_2") (pintype "passive"))
      (node (ref "C20") (pin "2") (pinfunction "2_2") (pintype "passive"))
      (node (ref "C21") (pin "-") (pinfunction "-_-") (pintype "passive"))
      (node (ref "C22") (pin "1") (pinfunction "1_1") (pintype "passive"))
      (node (ref "C23") (pin "-") (pinfunction "-_-") (pintype "passive"))
      (node (ref "C24") (pin "2") (pinfunction "2_2") (pintype "passive"))
      (node (ref "C25") (pin "-") (pinfunction "-_-") (pintype "passive"))
      (node (ref "C26") (pin "-") (pinfunction "-_-") (pintype "passive"))
      (node (ref "C27") (pin "-") (pinfunction "-_-") (pintype "passive"))
      (node (ref "C3") (pin "2") (pinfunction "2_2") (pintype "passive"))
      (node (ref "C32") (pin "1") (pinfunction "1_1") (pintype "passive"))
      (node (ref "C34") (pin "1") (pinfunction "1_1") (pintype "passive"))
      (node (ref "C4") (pin "2") (pinfunction "2_2") (pintype "passive"))
      (node (ref "C5") (pin "1") (pinfunction "1_1") (pintype "passive"))
      (node (ref "C6") (pin "1") (pinfunction "1_1") (pintype "passive"))
      (node (ref "C7") (pin "2") (pinfunction "2_2") (pintype "passive"))
      (node (ref "C9") (pin "1") (pinfunction "1_1") (pintype "passive"))
      (node (ref "D14") (pin "A") (pinfunction "A_A") (pintype "passive"))
      (node (ref "D15") (pin "1") (pinfunction "A1_1") (pintype "passive"))
      (node (ref "D16") (pin "1") (pinfunction "A1_1") (pintype "passive"))
      (node (ref "DD1") (pin "3") (pinfunction "VSS_3") (pintype "passive"))
      (node (ref "I2C") (pin "3") (pinfunction "3_3") (pintype "passive"))
      (node (ref "IC1") (pin "3") (pinfunction "GND_3") (pintype "power_in"))
      (node (ref "IC10") (pin "3") (pinfunction "GND_3") (pintype "bidirectional"))
      (node (ref "IC2") (pin "2") (pinfunction "GND_2") (pintype "passive"))
      (node (ref "IC2") (pin "2@1") (pinfunction "GND_2@1") (pintype "passive"))
      (node (ref "IC3") (pin "3") (pinfunction "GND_3") (pintype "bidirectional"))
      (node (ref "IC4") (pin "2") (pinfunction "GND_2") (pintype "passive"))
      (node (ref "IC4") (pin "2@1") (pinfunction "GND_2@1") (pintype "passive"))
      (node (ref "IC5") (pin "1") (pinfunction "B_1") (pintype "bidirectional"))
      (node (ref "IC5") (pin "2") (pinfunction "GND_2") (pintype "power_in"))
      (node (ref "IC6") (pin "1") (pinfunction "GND_1") (pintype "power_in"))
      (node (ref "IC7") (pin "2") (pinfunction "GND_2") (pintype "power_in"))
      (node (ref "IC8") (pin "1") (pinfunction "B_1") (pintype "bidirectional"))
      (node (ref "IC8") (pin "2") (pinfunction "GND_2") (pintype "power_in"))
      (node (ref "IC9") (pin "8") (pinfunction "VSS_8") (pintype "power_in"))
      (node (ref "Q11") (pin "1") (pinfunction "S_1") (pintype "passive"))
      (node (ref "Q11") (pin "2") (pinfunction "S_2") (pintype "passive"))
      (node (ref "Q11") (pin "3") (pinfunction "S_3") (pintype "passive"))
      (node (ref "Q13") (pin "2") (pinfunction "S_2") (pintype "passive"))
      (node (ref "Q14") (pin "2") (pinfunction "S_2") (pintype "passive"))
      (node (ref "Q2") (pin "2") (pinfunction "S_2") (pintype "passive"))
      (node (ref "Q3") (pin "2") (pinfunction "S_2") (pintype "passive"))
      (node (ref "Q4") (pin "2") (pinfunction "S_2") (pintype "passive"))
      (node (ref "Q9") (pin "1") (pinfunction "S_1") (pintype "passive"))
      (node (ref "Q9") (pin "2") (pinfunction "S_2") (pintype "passive"))
      (node (ref "Q9") (pin "3") (pinfunction "S_3") (pintype "passive"))
      (node (ref "R10") (pin "1") (pinfunction "1_1") (pintype "passive"))
      (node (ref "R13") (pin "2") (pinfunction "2_2") (pintype "passive"))
      (node (ref "R15") (pin "1") (pinfunction "1_1") (pintype "passive"))
      (node (ref "R16") (pin "1") (pinfunction "1_1") (pintype "passive"))
      (node (ref "R17") (pin "1") (pinfunction "1_1") (pintype "passive"))
      (node (ref "R27") (pin "1") (pinfunction "1_1") (pintype "passive"))
      (node (ref "R29") (pin "1") (pinfunction "1_1") (pintype "passive"))
      (node (ref "R33") (pin "2") (pinfunction "2_2") (pintype "passive"))
      (node (ref "R35") (pin "1") (pinfunction "1_1") (pintype "passive"))
      (node (ref "R37") (pin "2") (pinfunction "2_2") (pintype "passive"))
      (node (ref "R45") (pin "2") (pinfunction "2_2") (pintype "passive"))
      (node (ref "R59") (pin "2") (pinfunction "2_2") (pintype "passive"))
      (node (ref "R60") (pin "2") (pinfunction "2_2") (pintype "passive"))
      (node (ref "R61") (pin "2") (pinfunction "2_2") (pintype "passive"))
      (node (ref "R62") (pin "2") (pinfunction "2_2") (pintype "passive"))
      (node (ref "R70") (pin "2") (pinfunction "2_2") (pintype "passive"))
      (node (ref "R73") (pin "2") (pinfunction "2_2") (pintype "passive"))
      (node (ref "R76") (pin "2") (pinfunction "2_2") (pintype "passive"))
      (node (ref "R9") (pin "1") (pinfunction "1_1") (pintype "passive"))
      (node (ref "SWD") (pin "4") (pinfunction "4_4") (pintype "passive"))
      (node (ref "U2") (pin "23") (pinfunction "VSS_1_23") (pintype "power_in"))
      (node (ref "U2") (pin "35") (pinfunction "VSS_2_35") (pintype "power_in"))
      (node (ref "U2") (pin "47") (pinfunction "VSS_3_47") (pintype "power_in"))
      (node (ref "U2") (pin "8") (pinfunction "VSSA_8") (pintype "power_in"))
      (node (ref "UART") (pin "3") (pinfunction "3_3") (pintype "passive"))
      (node (ref "UART2") (pin "3") (pinfunction "3_3") (pintype "passive"))
      (node (ref "X0") (pin "14") (pinfunction "GND_14") (pintype "power_in"))
      (node (ref "X0") (pin "20") (pinfunction "GND_20") (pintype "power_in"))
      (node (ref "X0") (pin "25") (pinfunction "GND_25") (pintype "power_in"))
      (node (ref "X0") (pin "6") (pinfunction "GND_6") (pintype "power_in"))
      (node (ref "X0") (pin "9") (pinfunction "GND_9") (pintype "power_in"))
      (node (ref "X15") (pin "2") (pinfunction "KL_2") (pintype "passive"))
      (node (ref "X4") (pin "2") (pinfunction "KL_2") (pintype "passive"))
      (node (ref "X9") (pin "3") (pinfunction "KL_3") (pintype "passive"))
    )
    (net (code "29") (name "Net-(1W-1A-K)") (class "Default")
      (node (ref "1W-1") (pin "1") (pinfunction "K_1") (pintype "passive"))
      (node (ref "L1W1") (pin "A") (pinfunction "A_A") (pintype "passive"))
      (node (ref "Q8") (pin "3") (pinfunction "D_3") (pintype "passive"))
    )
    (net (code "30") (name "Net-(1W-1B-K)") (class "Default")
      (node (ref "1W-1") (pin "2") (pinfunction "K_2") (pintype "passive"))
      (node (ref "D15") (pin "3") (pinfunction "C1A2_3") (pintype "passive"))
      (node (ref "IC5") (pin "4") (pinfunction "X_4") (pintype "bidirectional"))
    )
    (net (code "31") (name "Net-(1W-2A-K)") (class "Default")
      (node (ref "1W-2") (pin "1") (pinfunction "K_1") (pintype "passive"))
      (node (ref "L1W2") (pin "A") (pinfunction "A_A") (pintype "passive"))
      (node (ref "Q10") (pin "3") (pinfunction "D_3") (pintype "passive"))
    )
    (net (code "32") (name "Net-(1W-2B-K)") (class "Default")
      (node (ref "1W-2") (pin "2") (pinfunction "K_2") (pintype "passive"))
      (node (ref "D16") (pin "3") (pinfunction "C1A2_3") (pintype "passive"))
      (node (ref "IC8") (pin "4") (pinfunction "X_4") (pintype "bidirectional"))
    )
    (net (code "33") (name "Net-(A0-P$1)") (class "Default")
      (node (ref "A0") (pin "2") (pinfunction "P$1_2") (pintype "bidirectional"))
      (node (ref "IC9") (pin "3") (pinfunction "A2_3") (pintype "input"))
    )
    (net (code "34") (name "Net-(C21-Pad+)") (class "Default")
      (node (ref "C21") (pin "+") (pinfunction "+_+") (pintype "passive"))
      (node (ref "K1") (pin "2") (pinfunction "2_2") (pintype "passive"))
      (node (ref "R26") (pin "2") (pinfunction "2_2") (pintype "passive"))
    )
    (net (code "35") (name "Net-(C25-Pad+)") (class "Default")
      (node (ref "C25") (pin "+") (pinfunction "+_+") (pintype "passive"))
      (node (ref "K6") (pin "2") (pinfunction "2_2") (pintype "passive"))
      (node (ref "R41") (pin "2") (pinfunction "2_2") (pintype "passive"))
    )
    (net (code "36") (name "Net-(IC1A-1W)") (class "Default")
      (node (ref "IC1") (pin "2") (pinfunction "1W_2") (pintype "open_collector"))
      (node (ref "IC5") (pin "3") (pinfunction "A_3") (pintype "bidirectional"))
      (node (ref "IC8") (pin "3") (pinfunction "A_3") (pintype "bidirectional"))
      (node (ref "Q7") (pin "3") (pinfunction "D_3") (pintype "passive"))
    )
    (net (code "37") (name "Net-(IC1A-PCT)") (class "Default")
      (node (ref "IC1") (pin "6") (pinfunction "PCT_6") (pintype "output"))
      (node (ref "Q7") (pin "1") (pinfunction "G_1") (pintype "passive"))
    )
    (net (code "38") (name "Net-(IC3-OUTF1)") (class "Default")
      (node (ref "IC3") (pin "5") (pinfunction "OUTF1_5") (pintype "bidirectional"))
      (node (ref "IC3") (pin "6") (pinfunction "OUTF2_6") (pintype "bidirectional"))
      (node (ref "X4") (pin "1") (pinfunction "KL_1") (pintype "passive"))
    )
    (net (code "39") (name "Net-(IC3-OUTR1)") (class "Default")
      (node (ref "IC3") (pin "7") (pinfunction "OUTR1_7") (pintype "bidirectional"))
      (node (ref "IC3") (pin "8") (pinfunction "OUTR2_8") (pintype "bidirectional"))
      (node (ref "X4") (pin "3") (pinfunction "KL_3") (pintype "passive"))
    )
    (net (code "40") (name "Net-(IC4-VO)") (class "Default")
      (node (ref "C17") (pin "2") (pinfunction "2_2") (pintype "passive"))
      (node (ref "C18") (pin "2") (pinfunction "2_2") (pintype "passive"))
      (node (ref "C23") (pin "+") (pinfunction "+_+") (pintype "passive"))
      (node (ref "C3") (pin "1") (pinfunction "1_1") (pintype "passive"))
      (node (ref "FB1") (pin "1") (pinfunction "1_1") (pintype "passive"))
      (node (ref "IC4") (pin "1") (pinfunction "VO_1") (pintype "passive"))
      (node (ref "R14") (pin "2") (pinfunction "2_2") (pintype "passive"))
      (node (ref "R8") (pin "2") (pinfunction "2_2") (pintype "passive"))
      (node (ref "SWD") (pin "1") (pinfunction "1_1") (pintype "passive"))
      (node (ref "U2") (pin "24") (pinfunction "VDD_1_24") (pintype "power_in"))
      (node (ref "U2") (pin "36") (pinfunction "VDD_2_36") (pintype "power_in"))
      (node (ref "U2") (pin "48") (pinfunction "VDD_3_48") (pintype "power_in"))
    )
    (net (code "41") (name "Net-(IC6-BST)") (class "Default")
      (node (ref "C8") (pin "1") (pinfunction "1_1") (pintype "passive"))
      (node (ref "IC6") (pin "6") (pinfunction "BST_6") (pintype "input"))
    )
    (net (code "42") (name "Net-(IC6-FB)") (class "Default")
      (node (ref "IC6") (pin "4") (pinfunction "FB_4") (pintype "input"))
      (node (ref "R10") (pin "2") (pinfunction "2_2") (pintype "passive"))
      (node (ref "R11") (pin "2") (pinfunction "2_2") (pintype "passive"))
    )
    (net (code "43") (name "Net-(IC6-SW)") (class "Default")
      (node (ref "C8") (pin "2") (pinfunction "2_2") (pintype "passive"))
      (node (ref "IC6") (pin "2") (pinfunction "SW_2") (pintype "passive"))
      (node (ref "L4.7") (pin "P$1") (pinfunction "1_P$1") (pintype "passive"))
    )
    (net (code "44") (name "Net-(IC9-P0)") (class "Default")
      (node (ref "IC9") (pin "4") (pinfunction "P0_4") (pintype "bidirectional"))
      (node (ref "R47") (pin "2") (pinfunction "2_2") (pintype "passive"))
      (node (ref "R62") (pin "1") (pinfunction "1_1") (pintype "passive"))
    )
    (net (code "45") (name "Net-(IC9-P1)") (class "Default")
      (node (ref "IC9") (pin "5") (pinfunction "P1_5") (pintype "bidirectional"))
      (node (ref "R44") (pin "2") (pinfunction "2_2") (pintype "passive"))
      (node (ref "R61") (pin "1") (pinfunction "1_1") (pintype "passive"))
    )
    (net (code "46") (name "Net-(IC9-P2)") (class "Default")
      (node (ref "IC9") (pin "6") (pinfunction "P2_6") (pintype "bidirectional"))
      (node (ref "R37") (pin "1") (pinfunction "1_1") (pintype "passive"))
      (node (ref "R84") (pin "2") (pinfunction "2_2") (pintype "passive"))
    )
    (net (code "47") (name "Net-(IC9-P3)") (class "Default")
      (node (ref "IC9") (pin "7") (pinfunction "P3_7") (pintype "bidirectional"))
      (node (ref "R73") (pin "1") (pinfunction "1_1") (pintype "passive"))
      (node (ref "R77") (pin "2") (pinfunction "2_2") (pintype "passive"))
    )
    (net (code "48") (name "Net-(IC9-P4)") (class "Default")
      (node (ref "IC9") (pin "9") (pinfunction "P4_9") (pintype "bidirectional"))
      (node (ref "R40") (pin "2") (pinfunction "2_2") (pintype "passive"))
      (node (ref "R59") (pin "1") (pinfunction "1_1") (pintype "passive"))
    )
    (net (code "49") (name "Net-(IC9-P5)") (class "Default")
      (node (ref "IC9") (pin "10") (pinfunction "P5_10") (pintype "bidirectional"))
      (node (ref "R43") (pin "2") (pinfunction "2_2") (pintype "passive"))
      (node (ref "R60") (pin "1") (pinfunction "1_1") (pintype "passive"))
    )
    (net (code "50") (name "Net-(IC10-OUTF1)") (class "Default")
      (node (ref "IC10") (pin "5") (pinfunction "OUTF1_5") (pintype "bidirectional"))
      (node (ref "IC10") (pin "6") (pinfunction "OUTF2_6") (pintype "bidirectional"))
      (node (ref "X15") (pin "1") (pinfunction "KL_1") (pintype "passive"))
    )
    (net (code "51") (name "Net-(IC10-OUTR1)") (class "Default")
      (node (ref "IC10") (pin "7") (pinfunction "OUTR1_7") (pintype "bidirectional"))
      (node (ref "IC10") (pin "8") (pinfunction "OUTR2_8") (pintype "bidirectional"))
      (node (ref "X15") (pin "3") (pinfunction "KL_3") (pintype "passive"))
    )
    (net (code "52") (name "Net-(K2A-PA)") (class "Default")
      (node (ref "K2") (pin "3") (pinfunction "PA_3") (pintype "passive"))
      (node (ref "K2") (pin "6") (pinfunction "PB_6") (pintype "passive"))
      (node (ref "X1") (pin "1") (pinfunction "KL_1") (pintype "passive"))
    )
    (net (code "53") (name "Net-(K2A-SA)") (class "Default")
      (node (ref "K2") (pin "4") (pinfunction "SA_4") (pintype "passive"))
      (node (ref "K2") (pin "5") (pinfunction "SB_5") (pintype "passive"))
      (node (ref "X1") (pin "2") (pinfunction "KL_2") (pintype "passive"))
    )
    (net (code "54") (name "Net-(K2B-2)") (class "Default")
      (node (ref "C27") (pin "+") (pinfunction "+_+") (pintype "passive"))
      (node (ref "K2") (pin "8") (pinfunction "2_8") (pintype "passive"))
      (node (ref "R74") (pin "2") (pinfunction "2_2") (pintype "passive"))
    )
    (net (code "55") (name "Net-(K3A-PA)") (class "Default")
      (node (ref "K3") (pin "3") (pinfunction "PA_3") (pintype "passive"))
      (node (ref "K3") (pin "6") (pinfunction "PB_6") (pintype "passive"))
      (node (ref "X2") (pin "1") (pinfunction "KL_1") (pintype "passive"))
    )
    (net (code "56") (name "Net-(K3A-SA)") (class "Default")
      (node (ref "K3") (pin "4") (pinfunction "SA_4") (pintype "passive"))
      (node (ref "K3") (pin "5") (pinfunction "SB_5") (pintype "passive"))
      (node (ref "X2") (pin "2") (pinfunction "KL_2") (pintype "passive"))
    )
    (net (code "57") (name "Net-(K3B-2)") (class "Default")
      (node (ref "C26") (pin "+") (pinfunction "+_+") (pintype "passive"))
      (node (ref "K3") (pin "8") (pinfunction "2_8") (pintype "passive"))
      (node (ref "R82") (pin "2") (pinfunction "2_2") (pintype "passive"))
    )
    (net (code "58") (name "Net-(L1W1-PadC)") (class "Default")
      (node (ref "L1W1") (pin "C") (pinfunction "C_C") (pintype "passive"))
      (node (ref "R76") (pin "1") (pinfunction "1_1") (pintype "passive"))
    )
    (net (code "59") (name "Net-(L1W2-PadC)") (class "Default")
      (node (ref "L1W2") (pin "C") (pinfunction "C_C") (pintype "passive"))
      (node (ref "R45") (pin "1") (pinfunction "1_1") (pintype "passive"))
    )
    (net (code "60") (name "Net-(L4.7-2)") (class "Default")
      (node (ref "C14") (pin "+") (pinfunction "+_+") (pintype "passive"))
      (node (ref "C22") (pin "2") (pinfunction "2_2") (pintype "passive"))
      (node (ref "C9") (pin "2") (pinfunction "2_2") (pintype "passive"))
      (node (ref "L4.7") (pin "P$2") (pinfunction "2_P$2") (pintype "passive"))
      (node (ref "R11") (pin "1") (pinfunction "1_1") (pintype "passive"))
      (node (ref "R5") (pin "2") (pinfunction "2_2") (pintype "passive"))
      (node (ref "X0") (pin "2") (pinfunction "5V_2") (pintype "power_in"))
      (node (ref "X0") (pin "4") (pinfunction "5V_4") (pintype "power_in"))
    )
    (net (code "61") (name "Net-(LED1-PadC)") (class "Default")
      (node (ref "LED1") (pin "C") (pinfunction "C_C") (pintype "passive"))
      (node (ref "R22") (pin "1") (pinfunction "1_1") (pintype "passive"))
    )
    (net (code "62") (name "Net-(LED2-PadC)") (class "Default")
      (node (ref "LED2") (pin "C") (pinfunction "C_C") (pintype "passive"))
      (node (ref "R23") (pin "1") (pinfunction "1_1") (pintype "passive"))
    )
    (net (code "63") (name "Net-(LED3-PadC)") (class "Default")
      (node (ref "LED3") (pin "C") (pinfunction "C_C") (pintype "passive"))
      (node (ref "R75") (pin "1") (pinfunction "1_1") (pintype "passive"))
    )
    (net (code "64") (name "Net-(LED4-PadC)") (class "Default")
      (node (ref "LED4") (pin "C") (pinfunction "C_C") (pintype "passive"))
      (node (ref "R83") (pin "1") (pinfunction "1_1") (pintype "passive"))
    )
    (net (code "65") (name "Net-(LED7-PadC)") (class "Default")
      (node (ref "LED7") (pin "C") (pinfunction "C_C") (pintype "passive"))
      (node (ref "R36") (pin "1") (pinfunction "1_1") (pintype "passive"))
    )
    (net (code "66") (name "Net-(LED8-PadC)") (class "Default")
      (node (ref "LED8") (pin "C") (pinfunction "C_C") (pintype "passive"))
      (node (ref "R42") (pin "1") (pinfunction "1_1") (pintype "passive"))
    )
    (net (code "67") (name "Net-(LED9-PadC)") (class "Default")
      (node (ref "LED9") (pin "C") (pinfunction "C_C") (pintype "passive"))
      (node (ref "R25") (pin "1") (pinfunction "1_1") (pintype "passive"))
    )
    (net (code "68") (name "Net-(LED10-PadC)") (class "Default")
      (node (ref "LED10") (pin "C") (pinfunction "C_C") (pintype "passive"))
      (node (ref "R64") (pin "1") (pinfunction "1_1") (pintype "passive"))
    )
    (net (code "69") (name "Net-(Q2-D)") (class "Default")
      (node (ref "Q2") (pin "3") (pinfunction "D_3") (pintype "passive"))
      (node (ref "R28") (pin "1") (pinfunction "1_1") (pintype "passive"))
    )
    (net (code "70") (name "Net-(Q2-G)") (class "Default")
      (node (ref "Q2") (pin "1") (pinfunction "G_1") (pintype "passive"))
      (node (ref "R71") (pin "2") (pinfunction "2_2") (pintype "passive"))
    )
    (net (code "71") (name "Net-(Q3-D)") (class "Default")
      (node (ref "D1") (pin "A") (pinfunction "A_A") (pintype "passive"))
      (node (ref "K1") (pin "1") (pinfunction "1_1") (pintype "passive"))
      (node (ref "Q3") (pin "3") (pinfunction "D_3") (pintype "passive"))
      (node (ref "R36") (pin "2") (pinfunction "2_2") (pintype "passive"))
    )
    (net (code "72") (name "Net-(Q3-G)") (class "Default")
      (node (ref "Q3") (pin "1") (pinfunction "G_1") (pintype "passive"))
      (node (ref "R40") (pin "1") (pinfunction "1_1") (pintype "passive"))
    )
    (net (code "73") (name "Net-(Q4-D)") (class "Default")
      (node (ref "D2") (pin "A") (pinfunction "A_A") (pintype "passive"))
      (node (ref "K6") (pin "1") (pinfunction "1_1") (pintype "passive"))
      (node (ref "Q4") (pin "3") (pinfunction "D_3") (pintype "passive"))
      (node (ref "R42") (pin "2") (pinfunction "2_2") (pintype "passive"))
    )
    (net (code "74") (name "Net-(Q4-G)") (class "Default")
      (node (ref "Q4") (pin "1") (pinfunction "G_1") (pintype "passive"))
      (node (ref "R43") (pin "1") (pinfunction "1_1") (pintype "passive"))
    )
    (net (code "75") (name "Net-(Q8-G)") (class "Default")
      (node (ref "Q8") (pin "1") (pinfunction "G_1") (pintype "passive"))
      (node (ref "R31") (pin "2") (pinfunction "2_2") (pintype "passive"))
    )
    (net (code "76") (name "Net-(Q9-G)") (class "Default")
      (node (ref "Q9") (pin "4") (pinfunction "G_4") (pintype "passive"))
      (node (ref "R44") (pin "1") (pinfunction "1_1") (pintype "passive"))
    )
    (net (code "77") (name "Net-(Q10-G)") (class "Default")
      (node (ref "Q10") (pin "1") (pinfunction "G_1") (pintype "passive"))
      (node (ref "R32") (pin "2") (pinfunction "2_2") (pintype "passive"))
    )
    (net (code "78") (name "Net-(Q11-G)") (class "Default")
      (node (ref "Q11") (pin "4") (pinfunction "G_4") (pintype "passive"))
      (node (ref "R47") (pin "1") (pinfunction "1_1") (pintype "passive"))
    )
    (net (code "79") (name "Net-(Q13-D)") (class "Default")
      (node (ref "D19") (pin "A") (pinfunction "A_A") (pintype "passive"))
      (node (ref "K2") (pin "1") (pinfunction "1_1") (pintype "passive"))
      (node (ref "Q13") (pin "3") (pinfunction "D_3") (pintype "passive"))
      (node (ref "R75") (pin "2") (pinfunction "2_2") (pintype "passive"))
    )
    (net (code "80") (name "Net-(Q13-G)") (class "Default")
      (node (ref "Q13") (pin "1") (pinfunction "G_1") (pintype "passive"))
      (node (ref "R77") (pin "1") (pinfunction "1_1") (pintype "passive"))
    )
    (net (code "81") (name "Net-(Q14-D)") (class "Default")
      (node (ref "D21") (pin "A") (pinfunction "A_A") (pintype "passive"))
      (node (ref "K3") (pin "1") (pinfunction "1_1") (pintype "passive"))
      (node (ref "Q14") (pin "3") (pinfunction "D_3") (pintype "passive"))
      (node (ref "R83") (pin "2") (pinfunction "2_2") (pintype "passive"))
    )
    (net (code "82") (name "Net-(Q14-G)") (class "Default")
      (node (ref "Q14") (pin "1") (pinfunction "G_1") (pintype "passive"))
      (node (ref "R84") (pin "1") (pinfunction "1_1") (pintype "passive"))
    )
    (net (code "83") (name "Net-(U2-VBAT)") (class "Default")
      (node (ref "C2") (pin "1") (pinfunction "1_1") (pintype "passive"))
      (node (ref "FB1") (pin "2") (pinfunction "2_2") (pintype "passive"))
      (node (ref "U2") (pin "1") (pinfunction "VBAT_1") (pintype "power_in"))
      (node (ref "U2") (pin "9") (pinfunction "VDDA_9") (pintype "power_in"))
    )
    (net (code "84") (name "Net-(X0-PWM1{slash}PA06)") (class "Default")
      (node (ref "R70") (pin "1") (pinfunction "1_1") (pintype "passive"))
      (node (ref "R71") (pin "1") (pinfunction "1_1") (pintype "passive"))
      (node (ref "X0") (pin "7") (pinfunction "PWM1/PA06_7") (pintype "bidirectional"))
    )
    (net (code "85") (name "Net-(X0-UART1_RX{slash}PG07)") (class "Default")
      (node (ref "R1") (pin "2") (pinfunction "2_2") (pintype "passive"))
      (node (ref "R3") (pin "2") (pinfunction "2_2") (pintype "passive"))
      (node (ref "UART") (pin "2") (pinfunction "2_2") (pintype "passive"))
      (node (ref "X0") (pin "10") (pinfunction "UART1_RX/PG07_10") (pintype "bidirectional"))
    )
    (net (code "86") (name "Net-(X0-UART1_TX{slash}PG06)") (class "Default")
      (node (ref "R2") (pin "2") (pinfunction "2_2") (pintype "passive"))
      (node (ref "R4") (pin "2") (pinfunction "2_2") (pintype "passive"))
      (node (ref "UART") (pin "1") (pinfunction "1_1") (pintype "passive"))
      (node (ref "X0") (pin "8") (pinfunction "UART1_TX/PG06_8") (pintype "bidirectional"))
    )
    (net (code "87") (name "Net-(X0-UART2_RX{slash}PA01)") (class "Default")
      (node (ref "UART2") (pin "2") (pinfunction "2_2") (pintype "passive"))
      (node (ref "X0") (pin "11") (pinfunction "UART2_RX/PA01_11") (pintype "bidirectional"))
    )
    (net (code "88") (name "Net-(X0-UART2_TX{slash}PA00)") (class "Default")
      (node (ref "UART2") (pin "1") (pinfunction "1_1") (pintype "passive"))
      (node (ref "X0") (pin "13") (pinfunction "UART2_TX/PA00_13") (pintype "bidirectional"))
    )
    (net (code "89") (name "Net-(X6A-KL)") (class "Default")
      (node (ref "K1") (pin "O") (pinfunction "O_O") (pintype "passive"))
      (node (ref "X6") (pin "1") (pinfunction "KL_1") (pintype "passive"))
    )
    (net (code "90") (name "Net-(X6B-KL)") (class "Default")
      (node (ref "K1") (pin "P") (pinfunction "P_P") (pintype "passive"))
      (node (ref "X6") (pin "2") (pinfunction "KL_2") (pintype "passive"))
    )
    (net (code "91") (name "Net-(X6C-KL)") (class "Default")
      (node (ref "K1") (pin "S") (pinfunction "S_S") (pintype "passive"))
      (node (ref "X6") (pin "3") (pinfunction "KL_3") (pintype "passive"))
    )
    (net (code "92") (name "Net-(X8A-KL)") (class "Default")
      (node (ref "K6") (pin "O") (pinfunction "O_O") (pintype "passive"))
      (node (ref "X8") (pin "1") (pinfunction "KL_1") (pintype "passive"))
    )
    (net (code "93") (name "Net-(X8B-KL)") (class "Default")
      (node (ref "K6") (pin "P") (pinfunction "P_P") (pintype "passive"))
      (node (ref "X8") (pin "2") (pinfunction "KL_2") (pintype "passive"))
    )
    (net (code "94") (name "Net-(X8C-KL)") (class "Default")
      (node (ref "K6") (pin "S") (pinfunction "S_S") (pintype "passive"))
      (node (ref "X8") (pin "3") (pinfunction "KL_3") (pintype "passive"))
    )
    (net (code "95") (name "Net-(X9A-KL)") (class "Default")
      (node (ref "D10") (pin "A") (pinfunction "A_A") (pintype "passive"))
      (node (ref "R30") (pin "1") (pinfunction "1_1") (pintype "passive"))
      (node (ref "X9") (pin "1") (pinfunction "KL_1") (pintype "passive"))
    )
    (net (code "96") (name "Net-(X10B-KL)") (class "Default")
      (node (ref "D3") (pin "A") (pinfunction "A_A") (pintype "passive"))
      (node (ref "Q9") (pin "5") (pinfunction "D_5") (pintype "passive"))
      (node (ref "Q9") (pin "6") (pinfunction "D_6") (pintype "passive"))
      (node (ref "Q9") (pin "7") (pinfunction "D_7") (pintype "passive"))
      (node (ref "Q9") (pin "8") (pinfunction "D_8") (pintype "passive"))
      (node (ref "R25") (pin "2") (pinfunction "2_2") (pintype "passive"))
      (node (ref "X10") (pin "2") (pinfunction "KL_2") (pintype "passive"))
    )
    (net (code "97") (name "Net-(X11B-KL)") (class "Default")
      (node (ref "D4") (pin "A") (pinfunction "A_A") (pintype "passive"))
      (node (ref "Q11") (pin "5") (pinfunction "D_5") (pintype "passive"))
      (node (ref "Q11") (pin "6") (pinfunction "D_6") (pintype "passive"))
      (node (ref "Q11") (pin "7") (pinfunction "D_7") (pintype "passive"))
      (node (ref "Q11") (pin "8") (pinfunction "D_8") (pintype "passive"))
      (node (ref "R64") (pin "2") (pinfunction "2_2") (pintype "passive"))
      (node (ref "X11") (pin "2") (pinfunction "KL_2") (pintype "passive"))
    )
    (net (code "98") (name "VDD") (class "Default")
      (node (ref "C20") (pin "1") (pinfunction "1_1") (pintype "passive"))
      (node (ref "C24") (pin "1") (pinfunction "1_1") (pintype "passive"))
      (node (ref "C4") (pin "1") (pinfunction "1_1") (pintype "passive"))
      (node (ref "C7") (pin "1") (pinfunction "1_1") (pintype "passive"))
      (node (ref "D14") (pin "C") (pinfunction "C_C") (pintype "passive"))
      (node (ref "D15") (pin "2") (pinfunction "C2_2") (pintype "passive"))
      (node (ref "D16") (pin "2") (pinfunction "C2_2") (pintype "passive"))
      (node (ref "DD1") (pin "2") (pinfunction "VDD_2") (pintype "input"))
      (node (ref "IC2") (pin "3") (pinfunction "VI_3") (pintype "input"))
      (node (ref "LED1") (pin "A") (pinfunction "A_A") (pintype "passive"))
      (node (ref "LED2") (pin "A") (pinfunction "A_A") (pintype "passive"))
      (node (ref "Q10") (pin "2") (pinfunction "S_2") (pintype "passive"))
      (node (ref "Q7") (pin "2") (pinfunction "S_2") (pintype "passive"))
      (node (ref "Q8") (pin "2") (pinfunction "S_2") (pintype "passive"))
      (node (ref "R27") (pin "2") (pinfunction "2_2") (pintype "passive"))
      (node (ref "R38") (pin "2") (pinfunction "2_2") (pintype "passive"))
      (node (ref "R39") (pin "2") (pinfunction "2_2") (pintype "passive"))
    )
    (net (code "99") (name "unconnected-(IC7-NC-Pad3)") (class "Default")
      (node (ref "IC7") (pin "3") (pinfunction "NC_3") (pintype "no_connect"))
    )
    (net (code "100") (name "unconnected-(IC9-~{INT}-Pad13)") (class "Default")
      (node (ref "IC9") (pin "13") (pinfunction "~{INT}_13") (pintype "output"))
    )
    (net (code "101") (name "unconnected-(K2A-OA-Pad2)") (class "Default")
      (node (ref "K2") (pin "2") (pinfunction "OA_2") (pintype "passive"))
    )
    (net (code "102") (name "unconnected-(K2A-OB-Pad7)") (class "Default")
      (node (ref "K2") (pin "7") (pinfunction "OB_7") (pintype "passive"))
    )
    (net (code "103") (name "unconnected-(K3A-OA-Pad2)") (class "Default")
      (node (ref "K3") (pin "2") (pinfunction "OA_2") (pintype "passive"))
    )
    (net (code "104") (name "unconnected-(K3A-OB-Pad7)") (class "Default")
      (node (ref "K3") (pin "7") (pinfunction "OB_7") (pintype "passive"))
    )
    (net (code "105") (name "unconnected-(U2-BOOT0-Pad44)") (class "Default")
      (node (ref "U2") (pin "44") (pinfunction "BOOT0_44") (pintype "input"))
    )
    (net (code "106") (name "unconnected-(U2-PA4-Pad14)") (class "Default")
      (node (ref "U2") (pin "14") (pinfunction "PA4_14") (pintype "bidirectional"))
    )
    (net (code "107") (name "unconnected-(U2-PA5-Pad15)") (class "Default")
      (node (ref "U2") (pin "15") (pinfunction "PA5_15") (pintype "bidirectional"))
    )
    (net (code "108") (name "unconnected-(U2-PA6-Pad16)") (class "Default")
      (node (ref "U2") (pin "16") (pinfunction "PA6_16") (pintype "bidirectional"))
    )
    (net (code "109") (name "unconnected-(U2-PA7-Pad17)") (class "Default")
      (node (ref "U2") (pin "17") (pinfunction "PA7_17") (pintype "bidirectional"))
    )
    (net (code "110") (name "unconnected-(U2-PA8-Pad29)") (class "Default")
      (node (ref "U2") (pin "29") (pinfunction "PA8_29") (pintype "bidirectional"))
    )
    (net (code "111") (name "unconnected-(U2-PA15-Pad38)") (class "Default")
      (node (ref "U2") (pin "38") (pinfunction "PA15_38") (pintype "bidirectional"))
    )
    (net (code "112") (name "unconnected-(U2-PB0-Pad18)") (class "Default")
      (node (ref "U2") (pin "18") (pinfunction "PB0_18") (pintype "bidirectional"))
    )
    (net (code "113") (name "unconnected-(U2-PB1-Pad19)") (class "Default")
      (node (ref "U2") (pin "19") (pinfunction "PB1_19") (pintype "bidirectional"))
    )
    (net (code "114") (name "unconnected-(U2-PB2-Pad20)") (class "Default")
      (node (ref "U2") (pin "20") (pinfunction "PB2_20") (pintype "bidirectional"))
    )
    (net (code "115") (name "unconnected-(U2-PB5-Pad41)") (class "Default")
      (node (ref "U2") (pin "41") (pinfunction "PB5_41") (pintype "bidirectional"))
    )
    (net (code "116") (name "unconnected-(U2-PB10-Pad21)") (class "Default")
      (node (ref "U2") (pin "21") (pinfunction "PB10_21") (pintype "bidirectional"))
    )
    (net (code "117") (name "unconnected-(U2-PB11-Pad22)") (class "Default")
      (node (ref "U2") (pin "22") (pinfunction "PB11_22") (pintype "bidirectional"))
    )
    (net (code "118") (name "unconnected-(U2-PB12-Pad25)") (class "Default")
      (node (ref "U2") (pin "25") (pinfunction "PB12_25") (pintype "bidirectional"))
    )
    (net (code "119") (name "unconnected-(U2-PB13-Pad26)") (class "Default")
      (node (ref "U2") (pin "26") (pinfunction "PB13_26") (pintype "bidirectional"))
    )
    (net (code "120") (name "unconnected-(U2-PC14-OSC32_IN-Pad3)") (class "Default")
      (node (ref "U2") (pin "3") (pinfunction "PC14-OSC32_IN_3") (pintype "bidirectional"))
    )
    (net (code "121") (name "unconnected-(U2-PC15-OSC32_OUT-Pad4)") (class "Default")
      (node (ref "U2") (pin "4") (pinfunction "PC15-OSC32_OUT_4") (pintype "bidirectional"))
    )
    (net (code "122") (name "unconnected-(U2-PD0-OSC_IN-Pad5)") (class "Default")
      (node (ref "U2") (pin "5") (pinfunction "PD0-OSC_IN_5") (pintype "input"))
    )
    (net (code "123") (name "unconnected-(U2-PD1-OSC_OUT-Pad6)") (class "Default")
      (node (ref "U2") (pin "6") (pinfunction "PD1-OSC_OUT_6") (pintype "output"))
    )
    (net (code "124") (name "unconnected-(X0-PA13{slash}SPI1_CS-Pad24)") (class "Default")
      (node (ref "X0") (pin "24") (pinfunction "PA13/SPI1_CS_24") (pintype "bidirectional"))
    )
    (net (code "125") (name "unconnected-(X0-PA14{slash}SPI1_CLK-Pad23)") (class "Default")
      (node (ref "X0") (pin "23") (pinfunction "PA14/SPI1_CLK_23") (pintype "bidirectional"))
    )
    (net (code "126") (name "unconnected-(X0-PA15{slash}SPI1_MOSI-Pad19)") (class "Default")
      (node (ref "X0") (pin "19") (pinfunction "PA15/SPI1_MOSI_19") (pintype "bidirectional"))
    )
    (net (code "127") (name "unconnected-(X0-PA16{slash}SPI1_MISO-Pad21)") (class "Default")
      (node (ref "X0") (pin "21") (pinfunction "PA16/SPI1_MISO_21") (pintype "bidirectional"))
    )
    (net (code "128") (name "unconnected-(X0-PA18{slash}TWI1_SCL-Pad18)") (class "Default")
      (node (ref "X0") (pin "18") (pinfunction "PA18/TWI1_SCL_18") (pintype "bidirectional"))
    )
    (net (code "129") (name "unconnected-(X0-PA19{slash}TWI1_SDA-Pad16)") (class "Default")
      (node (ref "X0") (pin "16") (pinfunction "PA19/TWI1_SDA_16") (pintype "bidirectional"))
    )
    (net (code "130") (name "unconnected-(X0-SIM_DET{slash}PA_EINT10{slash}PA10-Pad26)") (class "Default")
      (node (ref "X0") (pin "26") (pinfunction "SIM_DET/PA_EINT10/PA10_26") (pintype "bidirectional"))
    )
    (net (code "131") (name "unconnected-(X0-UART2_CTS{slash}PA03-Pad15)") (class "Default")
      (node (ref "X0") (pin "15") (pinfunction "UART2_CTS/PA03_15") (pintype "bidirectional"))
    )
    (net (code "132") (name "unconnected-(X0-UART2_RTS{slash}PA02-Pad22)") (class "Default")
      (node (ref "X0") (pin "22") (pinfunction "UART2_RTS/PA02_22") (pintype "bidirectional"))
    )
  )
)
